# Sheet2.net
KiCad netlist of a schematic drawn in Altium Designer
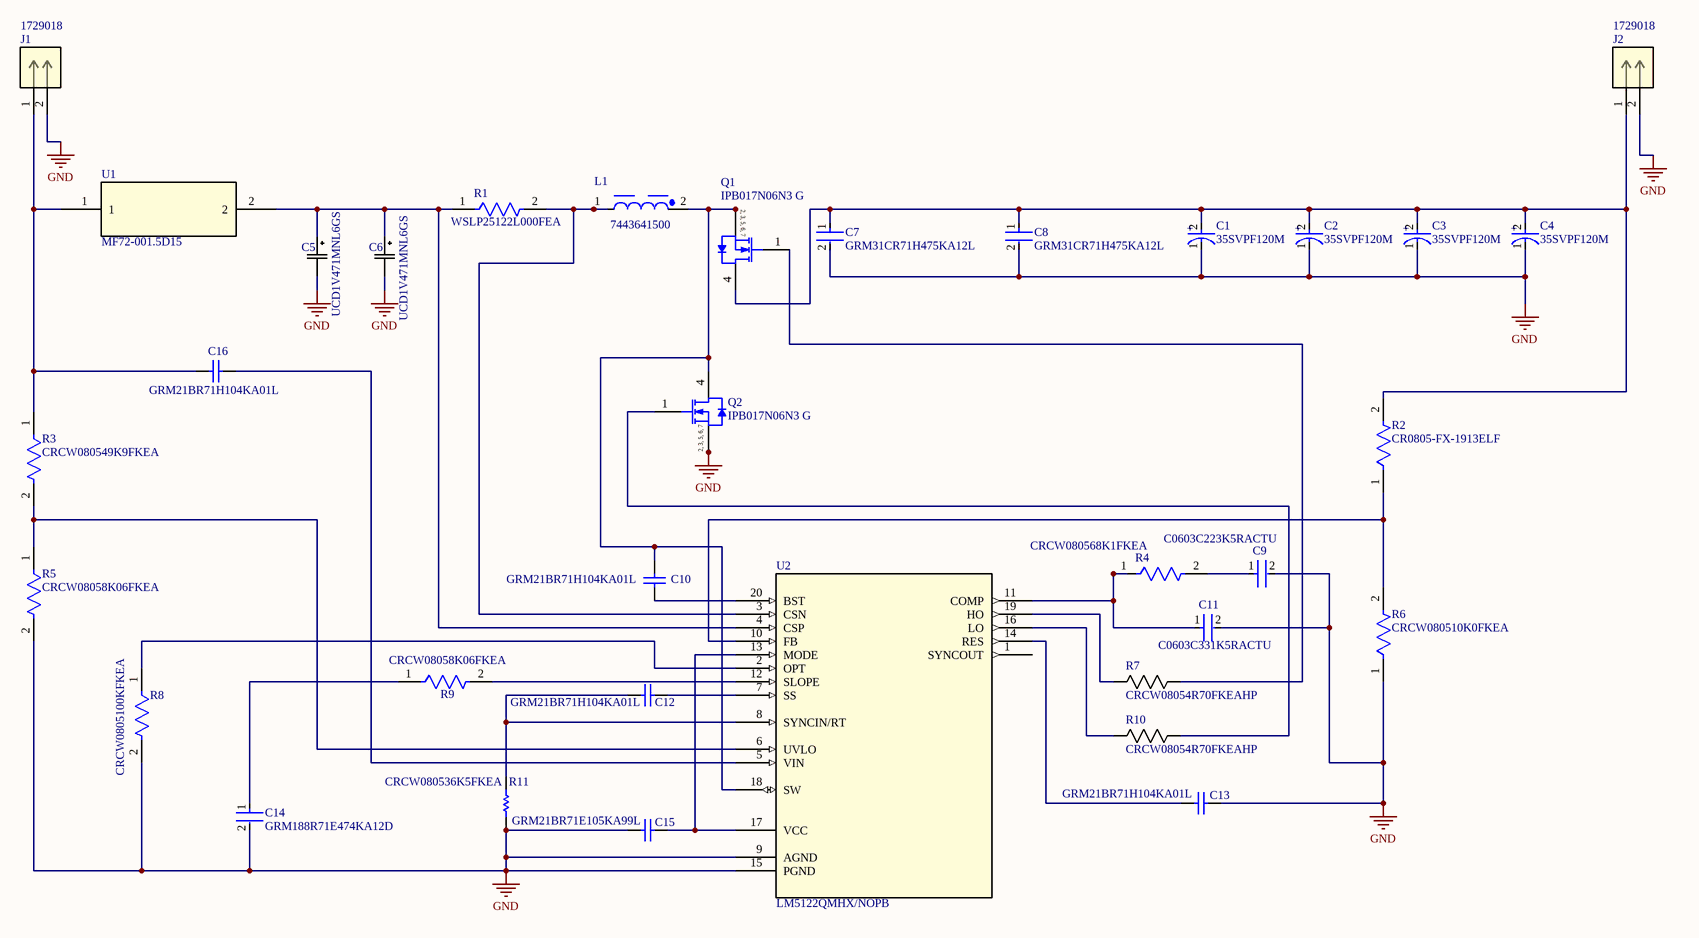
[diagram p0: Sheet2.SchDoc]

(export (version "E")
  (design (tool "Eeschema 10.0.6"))
  (components
    (comp (ref "C1")
      (value "35SVPF120M")
      (footprint "FP-OS-CON-SMT-F12-MFG")
      (description "Conductive Polymer Aluminum Solid Capacitors (OS-CON) 120uF ±20% 35V RADIAL SMT 10x12.6mm")
      (fields (field (name "VOLTAGE") "35V") (field (name "TOLERANCE") "20%"))
      (libsource (lib "Altium Content Vault") (part "a7907c86e72a156c28511143de7831b"))
    )
    (comp (ref "C2")
      (value "35SVPF120M")
      (footprint "FP-OS-CON-SMT-F12-MFG")
      (description "Conductive Polymer Aluminum Solid Capacitors (OS-CON) 120uF ±20% 35V RADIAL SMT 10x12.6mm")
      (fields (field (name "VOLTAGE") "35V") (field (name "TOLERANCE") "20%"))
      (libsource (lib "Altium Content Vault") (part "a7907c86e72a156c28511143de7831b"))
    )
    (comp (ref "C3")
      (value "35SVPF120M")
      (footprint "FP-OS-CON-SMT-F12-MFG")
      (description "Conductive Polymer Aluminum Solid Capacitors (OS-CON) 120uF ±20% 35V RADIAL SMT 10x12.6mm")
      (fields (field (name "VOLTAGE") "35V") (field (name "TOLERANCE") "20%"))
      (libsource (lib "Altium Content Vault") (part "a7907c86e72a156c28511143de7831b"))
    )
    (comp (ref "C4")
      (value "35SVPF120M")
      (footprint "FP-OS-CON-SMT-F12-MFG")
      (description "Conductive Polymer Aluminum Solid Capacitors (OS-CON) 120uF ±20% 35V RADIAL SMT 10x12.6mm")
      (fields (field (name "VOLTAGE") "35V") (field (name "TOLERANCE") "20%"))
      (libsource (lib "Altium Content Vault") (part "a7907c86e72a156c28511143de7831b"))
    )
    (comp (ref "C5")
      (value "UCD1V471MNL6GS")
      (footprint "CAP_UCD_10X13P5_NCH")
      (description "No Description Available")
      (fields (field (name "COPYRIGHT") "Copyright (C) 2026 Ultra Librarian. All rights reserved."))
      (libsource (lib "UCD1V471MNL6GS") (part "UCD1V471MNL6GS"))
    )
    (comp (ref "C6")
      (value "UCD1V471MNL6GS")
      (footprint "CAP_UCD_10X13P5_NCH")
      (description "No Description Available")
      (fields (field (name "COPYRIGHT") "Copyright (C) 2026 Ultra Librarian. All rights reserved."))
      (libsource (lib "UCD1V471MNL6GS") (part "UCD1V471MNL6GS"))
    )
    (comp (ref "C7")
      (value "GRM31CR71H475KA12L")
      (footprint "FP-GRM31C-0_2-e0_3_0_8-IPC_C")
      (description "Chip Multilayer Ceramic Capacitors for General Purpose, 1206, 4.7uF, X7R, 15%, 10%, 50V")
      (fields (field (name "VOLTAGE") "50V") (field (name "TOLERANCE") "10%"))
      (libsource (lib "Altium Content Vault") (part "02cd4be3c70576c341d710602a673aa"))
    )
    (comp (ref "C8")
      (value "GRM31CR71H475KA12L")
      (footprint "FP-GRM31C-0_2-e0_3_0_8-IPC_C")
      (description "Chip Multilayer Ceramic Capacitors for General Purpose, 1206, 4.7uF, X7R, 15%, 10%, 50V")
      (fields (field (name "VOLTAGE") "50V") (field (name "TOLERANCE") "10%"))
      (libsource (lib "Altium Content Vault") (part "02cd4be3c70576c341d710602a673aa"))
    )
    (comp (ref "C9")
      (value "C0603C223K5RACTU")
      (footprint "FP-C0603C-CF-MFG")
      (description "Ceramic Capacitor 0.022Uf 50V, X7R, 10%, 0603, Full Reel")
      (fields
        (field (name "OCTOPART") "https://octopart.com/c0603c223k5ractu-kemet-97352")
        (field (name "TOLERANCE") "0.1")
      )
      (libsource (lib "Altium Content Vault") (part "b4654b650e69147ec39a6b967a45e02"))
    )
    (comp (ref "C10")
      (value "GRM21BR71H104KA01L")
      (footprint "CAPC2013X135X45ML10T25")
      (description "Chip Capacitor, 0.1 uF, +/- 10%, 50 V, -55 to 125 degC, 0805 (2012 Metric), RoHS, Tape and Reel")
      (fields (field (name "VOLTAGE") "50V") (field (name "TOLERANCE") "10%"))
      (libsource (lib "Altium Content Vault") (part "CAP-NP-2"))
    )
    (comp (ref "C11")
      (value "C0603C331K5RACTU")
      (footprint "FP-C0603C-CF-MFG")
      (description "CAP CER 330PF 50V X7R 0603")
      (fields (field (name "MANUFACTURER") "KEMET") (field (name "TOLERANCE") "0.1"))
      (libsource (lib "Altium Content Vault") (part "b4654b650e69147ec39a6b967a45e02"))
    )
    (comp (ref "C12")
      (value "GRM21BR71H104KA01L")
      (footprint "CAPC2013X135X45ML10T25")
      (description "Chip Capacitor, 0.1 uF, +/- 10%, 50 V, -55 to 125 degC, 0805 (2012 Metric), RoHS, Tape and Reel")
      (fields (field (name "VOLTAGE") "50V") (field (name "TOLERANCE") "10%"))
      (libsource (lib "Altium Content Vault") (part "CAP-NP-2"))
    )
    (comp (ref "C13")
      (value "GRM21BR71H104KA01L")
      (footprint "CAPC2013X135X45ML10T25")
      (description "Chip Capacitor, 0.1 uF, +/- 10%, 50 V, -55 to 125 degC, 0805 (2012 Metric), RoHS, Tape and Reel")
      (fields (field (name "VOLTAGE") "50V") (field (name "TOLERANCE") "10%"))
      (libsource (lib "Altium Content Vault") (part "CAP-NP-2"))
    )
    (comp (ref "C14")
      (value "GRM188R71E474KA12D")
      (footprint "FP-GRM188-0_1-e0_2_0_5-MFG")
      (description "Chip Multilayer Ceramic Capacitors for General Purpose, 0603, 0.47uF, X7R, 15%, 10%, 25V")
      (fields (field (name "TOLERANCE") "10%") (field (name "VOLTAGE") "50V"))
      (libsource (lib "Altium Content Vault") (part "11868f565c42a9108669ba33697ecf6"))
    )
    (comp (ref "C15")
      (value "GRM21BR71E105KA99L")
      (footprint "CAPC2013X140X45NL15T25")
      (fields (field (name "MANUFACTURER") "Murata"))
      (libsource (lib "Altium Content Vault") (part "CAP"))
    )
    (comp (ref "C16")
      (value "GRM21BR71H104KA01L")
      (footprint "CAPC2013X135X45ML10T25")
      (description "Chip Capacitor, 0.1 uF, +/- 10%, 50 V, -55 to 125 degC, 0805 (2012 Metric), RoHS, Tape and Reel")
      (fields (field (name "VOLTAGE") "50V") (field (name "TOLERANCE") "10%"))
      (libsource (lib "Altium Content Vault") (part "CAP-NP-2"))
    )
    (comp (ref "J1")
      (value "1729018")
      (footprint "CONN_1729018_PXC")
      (fields (field (name "COPYRIGHT") "Copyright (C) 2025 Ultra Librarian. All rights reserved."))
      (libsource (lib "1729018") (part "1729018"))
    )
    (comp (ref "J2")
      (value "1729018")
      (footprint "CONN_1729018_PXC")
      (fields (field (name "COPYRIGHT") "Copyright (C) 2025 Ultra Librarian. All rights reserved."))
      (libsource (lib "1729018") (part "1729018"))
    )
    (comp (ref "L1")
      (value "7443641500")
      (footprint "WE-HCF_2818")
      (description "PowerChoke Shielded Wirewound 15uH 15% 100KHz Ferrite 30A 0.00264Ohm DCR Automotive Tray")
      (fields (field (name "TOLERANCE") "15%"))
      (libsource (lib "Altium Content Vault") (part "WE-HCF_2818"))
    )
    (comp (ref "Q1")
      (value "IPB017N06N3 G")
      (footprint "INF-PG-TO-263-7-2_N")
      (fields (field (name "MANUFACTURER") "Infineon"))
      (libsource (lib "Altium Content Vault") (part "INF-NEMOS-GSSDSSS-7"))
    )
    (comp (ref "Q2")
      (value "IPB017N06N3 G")
      (footprint "INF-PG-TO-263-7-2_N")
      (fields (field (name "MANUFACTURER") "Infineon"))
      (libsource (lib "Altium Content Vault") (part "INF-NEMOS-GSSDSSS-7"))
    )
    (comp (ref "R1")
      (value "WSLP25122L000FEA")
      (footprint "FP-WSLP2512-0R001-0R0049-MFG")
      (description "RES 0.002 OHM 1% 3W 2512")
      (fields (field (name "TOLERANCE") "1%"))
      (libsource (lib "Altium Content Vault") (part "1029c3af85768c4190bb7ad29bc67b5"))
    )
    (comp (ref "R2")
      (value "CR0805-FX-1913ELF")
      (footprint "FP-CR0805-IPC_B")
      (description "Thick Film Chip Resistors 0805 191kΩ 0.125W 1% 100ppm/°C")
      (fields (field (name "TOLERANCE") "1%"))
      (libsource (lib "Altium Content Vault") (part "1029c3af85768c4190bb7ad29bc67b5"))
    )
    (comp (ref "R3")
      (value "CRCW080549K9FKEA")
      (footprint "FP-CRCW0805-e3-IPC_C")
      (description "RES Thick Film, 49.9kΩ, 1%, 0.125W, 100ppm/°C, 0805")
      (fields (field (name "TOLERANCE") "1%"))
      (libsource (lib "Altium Content Vault") (part "1029c3af85768c4190bb7ad29bc67b5"))
    )
    (comp (ref "R4")
      (value "CRCW080568K1FKEA")
      (footprint "FP-CRCW0805-e3-MFG")
      (description "RES Thick Film, 68.1kΩ, 1%, 0.125W, 100ppm/°C, 0805")
      (fields (field (name "TOLERANCE") "1%"))
      (libsource (lib "Altium Content Vault") (part "1029c3af85768c4190bb7ad29bc67b5"))
    )
    (comp (ref "R5")
      (value "CRCW08058K06FKEA")
      (footprint "FP-CRCW0805-e3-MFG")
      (description "RES Thick Film, 8.06kΩ, 1%, 0.125W, 100ppm/°C, 0805")
      (fields (field (name "TOLERANCE") "1%"))
      (libsource (lib "Altium Content Vault") (part "1029c3af85768c4190bb7ad29bc67b5"))
    )
    (comp (ref "R6")
      (value "CRCW080510K0FKEA")
      (footprint "FP-CRCW0805-e3-IPC_A")
      (description "RES Thick Film, 10kΩ, 1%, 0.125W, 100ppm/°C, 0805")
      (fields (field (name "TOLERANCE") "1%"))
      (libsource (lib "Altium Content Vault") (part "1029c3af85768c4190bb7ad29bc67b5"))
    )
    (comp (ref "R7")
      (value "CRCW08054R70FKEAHP")
      (footprint "RES_CRCW_0805_VIS")
      (description "CRCW0805-HP 100 4R7 1% ET1 E3")
      (fields (field (name "COPYRIGHT") "Copyright (C) 2025 Ultra Librarian. All rights reserved."))
      (libsource (lib "CRCW08054R70FKEAHP") (part "CRCW08054R70FKEAHP"))
    )
    (comp (ref "R8")
      (value "CRCW0805100KFKEA")
      (footprint "FP-CRCW0805-e3-MFG")
      (description "RES Thick Film, 100kΩ, 1%, 0.125W, 100ppm/°C, 0805")
      (fields (field (name "TOLERANCE") "1%"))
      (libsource (lib "Altium Content Vault") (part "1029c3af85768c4190bb7ad29bc67b5"))
    )
    (comp (ref "R9")
      (value "CRCW08058K06FKEA")
      (footprint "FP-CRCW0805-e3-MFG")
      (description "RES Thick Film, 8.06kΩ, 1%, 0.125W, 100ppm/°C, 0805")
      (fields (field (name "TOLERANCE") "1%"))
      (libsource (lib "Altium Content Vault") (part "1029c3af85768c4190bb7ad29bc67b5"))
    )
    (comp (ref "R10")
      (value "CRCW08054R70FKEAHP")
      (footprint "RES_CRCW_0805_VIS")
      (description "CRCW0805-HP 100 4R7 1% ET1 E3")
      (fields (field (name "COPYRIGHT") "Copyright (C) 2025 Ultra Librarian. All rights reserved."))
      (libsource (lib "CRCW08054R70FKEAHP") (part "CRCW08054R70FKEAHP"))
    )
    (comp (ref "R11")
      (value "CRCW080536K5FKEA")
      (footprint "RESC2013X50X30ML20T20")
      (fields (field (name "MANUFACTURER") "Vishay Dale"))
      (libsource (lib "Altium Content Vault") (part "RES"))
    )
    (comp (ref "U1")
      (value "MF72-001.5D15")
      (footprint "MF72-001.5D15_CTM")
      (description "Description")
      (fields (field (name "COPYRIGHT") "Copyright (C) 2026 Ultra Librarian. All rights reserved."))
      (libsource (lib "MF72-001P5D15") (part "MF72-001.5D15"))
    )
    (comp (ref "U2")
      (value "LM5122QMHX/NOPB")
      (footprint "PWP20_3P0X4P2-M")
      (fields (field (name "COPYRIGHT") "Copyright (C) 2026 Ultra Librarian. All rights reserved."))
      (libsource (lib "LM5122QMHXNOPB") (part "LM5122QMHXNOPB"))
    )
  )
  (nets
    (net (code "1") (name "GND") (class "Default")
      (node (ref "C1") (pin "1") (pinfunction "C_1") (pintype "passive"))
      (node (ref "C11") (pin "2") (pinfunction "2_2") (pintype "passive"))
      (node (ref "C13") (pin "2") (pinfunction "2_2") (pintype "passive"))
      (node (ref "C14") (pin "2") (pinfunction "2_2") (pintype "passive"))
      (node (ref "C15") (pin "1") (pinfunction "1_1") (pintype "passive"))
      (node (ref "C2") (pin "1") (pinfunction "C_1") (pintype "passive"))
      (node (ref "C3") (pin "1") (pinfunction "C_1") (pintype "passive"))
      (node (ref "C4") (pin "1") (pinfunction "C_1") (pintype "passive"))
      (node (ref "C5") (pin "2") (pinfunction "2_2") (pintype "passive"))
      (node (ref "C6") (pin "2") (pinfunction "2_2") (pintype "passive"))
      (node (ref "C7") (pin "2") (pinfunction "2_2") (pintype "passive"))
      (node (ref "C8") (pin "2") (pinfunction "2_2") (pintype "passive"))
      (node (ref "C9") (pin "2") (pinfunction "2_2") (pintype "passive"))
      (node (ref "J1") (pin "2") (pinfunction "2_2") (pintype "passive"))
      (node (ref "J2") (pin "2") (pinfunction "2_2") (pintype "passive"))
      (node (ref "Q2") (pin "2") (pinfunction "SOURCE_2") (pintype "passive"))
      (node (ref "Q2") (pin "3") (pinfunction "SOURCE_3") (pintype "passive"))
      (node (ref "Q2") (pin "5") (pinfunction "SOURCE_5") (pintype "passive"))
      (node (ref "Q2") (pin "6") (pinfunction "SOURCE_6") (pintype "passive"))
      (node (ref "Q2") (pin "7") (pinfunction "SOURCE_7") (pintype "passive"))
      (node (ref "R11") (pin "1") (pinfunction "1_1") (pintype "passive"))
      (node (ref "R5") (pin "2") (pinfunction "2_2") (pintype "passive"))
      (node (ref "R6") (pin "1") (pinfunction "1_1") (pintype "passive"))
      (node (ref "R8") (pin "2") (pinfunction "2_2") (pintype "passive"))
      (node (ref "U2") (pin "15") (pinfunction "PGND_15") (pintype "power_in"))
      (node (ref "U2") (pin "9") (pinfunction "AGND_9") (pintype "power_in"))
    )
    (net (code "2") (name "Net-(C1-A)") (class "Default")
      (node (ref "C1") (pin "2") (pinfunction "A_2") (pintype "passive"))
      (node (ref "C2") (pin "2") (pinfunction "A_2") (pintype "passive"))
      (node (ref "C3") (pin "2") (pinfunction "A_2") (pintype "passive"))
      (node (ref "C4") (pin "2") (pinfunction "A_2") (pintype "passive"))
      (node (ref "C7") (pin "1") (pinfunction "1_1") (pintype "passive"))
      (node (ref "C8") (pin "1") (pinfunction "1_1") (pintype "passive"))
      (node (ref "J2") (pin "1") (pinfunction "1_1") (pintype "passive"))
      (node (ref "Q1") (pin "4") (pinfunction "DRAIN_4") (pintype "passive"))
      (node (ref "R2") (pin "2") (pinfunction "2_2") (pintype "passive"))
    )
    (net (code "3") (name "Net-(C9-Pad1)") (class "Default")
      (node (ref "C9") (pin "1") (pinfunction "1_1") (pintype "passive"))
      (node (ref "R4") (pin "2") (pinfunction "2_2") (pintype "passive"))
    )
    (net (code "4") (name "Net-(C14-Pad1)") (class "Default")
      (node (ref "C14") (pin "1") (pinfunction "1_1") (pintype "passive"))
      (node (ref "R9") (pin "1") (pinfunction "1_1") (pintype "passive"))
    )
    (net (code "5") (name "Net-(C16-Pad1)") (class "Default")
      (node (ref "C16") (pin "1") (pinfunction "1_1") (pintype "passive"))
      (node (ref "J1") (pin "1") (pinfunction "1_1") (pintype "passive"))
      (node (ref "R3") (pin "1") (pinfunction "1_1") (pintype "passive"))
      (node (ref "U1") (pin "1") (pinfunction "1_1") (pintype "passive"))
    )
    (net (code "6") (name "Net-(Q1-GATE)") (class "Default")
      (node (ref "Q1") (pin "1") (pinfunction "GATE_1") (pintype "passive"))
      (node (ref "R7") (pin "1") (pinfunction "1_1") (pintype "passive"))
    )
    (net (code "7") (name "Net-(Q2-DRAIN)") (class "Default")
      (node (ref "C10") (pin "1") (pinfunction "1_1") (pintype "passive"))
      (node (ref "L1") (pin "2") (pinfunction "2_2") (pintype "passive"))
      (node (ref "Q1") (pin "2") (pinfunction "SOURCE_2") (pintype "passive"))
      (node (ref "Q1") (pin "3") (pinfunction "SOURCE_3") (pintype "passive"))
      (node (ref "Q1") (pin "5") (pinfunction "SOURCE_5") (pintype "passive"))
      (node (ref "Q1") (pin "6") (pinfunction "SOURCE_6") (pintype "passive"))
      (node (ref "Q1") (pin "7") (pinfunction "SOURCE_7") (pintype "passive"))
      (node (ref "Q2") (pin "4") (pinfunction "DRAIN_4") (pintype "passive"))
      (node (ref "U2") (pin "18") (pinfunction "SW_18") (pintype "bidirectional"))
    )
    (net (code "8") (name "Net-(Q2-GATE)") (class "Default")
      (node (ref "Q2") (pin "1") (pinfunction "GATE_1") (pintype "passive"))
      (node (ref "R10") (pin "1") (pinfunction "1_1") (pintype "passive"))
    )
    (net (code "9") (name "Net-(U2-BST)") (class "Default")
      (node (ref "C10") (pin "2") (pinfunction "2_2") (pintype "passive"))
      (node (ref "U2") (pin "20") (pinfunction "BST_20") (pintype "input"))
    )
    (net (code "10") (name "Net-(U2-COMP)") (class "Default")
      (node (ref "C11") (pin "1") (pinfunction "1_1") (pintype "passive"))
      (node (ref "R4") (pin "1") (pinfunction "1_1") (pintype "passive"))
      (node (ref "U2") (pin "11") (pinfunction "COMP_11") (pintype "output"))
    )
    (net (code "11") (name "Net-(U2-CSN)") (class "Default")
      (node (ref "L1") (pin "1") (pinfunction "1_1") (pintype "passive"))
      (node (ref "R1") (pin "2") (pinfunction "2_2") (pintype "passive"))
      (node (ref "U2") (pin "3") (pinfunction "CSN_3") (pintype "input"))
    )
    (net (code "12") (name "Net-(U2-CSP)") (class "Default")
      (node (ref "C5") (pin "1") (pinfunction "1_1") (pintype "passive"))
      (node (ref "C6") (pin "1") (pinfunction "1_1") (pintype "passive"))
      (node (ref "R1") (pin "1") (pinfunction "1_1") (pintype "passive"))
      (node (ref "U1") (pin "2") (pinfunction "2_2") (pintype "passive"))
      (node (ref "U2") (pin "4") (pinfunction "CSP_4") (pintype "input"))
    )
    (net (code "13") (name "Net-(U2-FB)") (class "Default")
      (node (ref "R2") (pin "1") (pinfunction "1_1") (pintype "passive"))
      (node (ref "R6") (pin "2") (pinfunction "2_2") (pintype "passive"))
      (node (ref "U2") (pin "10") (pinfunction "FB_10") (pintype "input"))
    )
    (net (code "14") (name "Net-(U2-HO)") (class "Default")
      (node (ref "R7") (pin "2") (pinfunction "2_2") (pintype "passive"))
      (node (ref "U2") (pin "19") (pinfunction "HO_19") (pintype "output"))
    )
    (net (code "15") (name "Net-(U2-LO)") (class "Default")
      (node (ref "R10") (pin "2") (pinfunction "2_2") (pintype "passive"))
      (node (ref "U2") (pin "16") (pinfunction "LO_16") (pintype "output"))
    )
    (net (code "16") (name "Net-(U2-MODE)") (class "Default")
      (node (ref "C15") (pin "2") (pinfunction "2_2") (pintype "passive"))
      (node (ref "U2") (pin "13") (pinfunction "MODE_13") (pintype "input"))
      (node (ref "U2") (pin "17") (pinfunction "VCC_17") (pintype "power_in"))
    )
    (net (code "17") (name "Net-(U2-OPT)") (class "Default")
      (node (ref "R8") (pin "1") (pinfunction "1_1") (pintype "passive"))
      (node (ref "U2") (pin "2") (pinfunction "OPT_2") (pintype "input"))
    )
    (net (code "18") (name "Net-(U2-RES)") (class "Default")
      (node (ref "C13") (pin "1") (pinfunction "1_1") (pintype "passive"))
      (node (ref "U2") (pin "14") (pinfunction "RES_14") (pintype "output"))
    )
    (net (code "19") (name "Net-(U2-SLOPE)") (class "Default")
      (node (ref "R9") (pin "2") (pinfunction "2_2") (pintype "passive"))
      (node (ref "U2") (pin "12") (pinfunction "SLOPE_12") (pintype "input"))
    )
    (net (code "20") (name "Net-(U2-SS)") (class "Default")
      (node (ref "C12") (pin "2") (pinfunction "2_2") (pintype "passive"))
      (node (ref "U2") (pin "7") (pinfunction "SS_7") (pintype "input"))
    )
    (net (code "21") (name "Net-(U2-SYNCIN{slash}RT)") (class "Default")
      (node (ref "C12") (pin "1") (pinfunction "1_1") (pintype "passive"))
      (node (ref "R11") (pin "2") (pinfunction "2_2") (pintype "passive"))
      (node (ref "U2") (pin "8") (pinfunction "SYNCIN/RT_8") (pintype "input"))
    )
    (net (code "22") (name "Net-(U2-UVLO)") (class "Default")
      (node (ref "R3") (pin "2") (pinfunction "2_2") (pintype "passive"))
      (node (ref "R5") (pin "1") (pinfunction "1_1") (pintype "passive"))
      (node (ref "U2") (pin "6") (pinfunction "UVLO_6") (pintype "input"))
    )
    (net (code "23") (name "Net-(U2-VIN)") (class "Default")
      (node (ref "C16") (pin "2") (pinfunction "2_2") (pintype "passive"))
      (node (ref "U2") (pin "5") (pinfunction "VIN_5") (pintype "input"))
    )
    (net (code "24") (name "unconnected-(U2-SYNCOUT-Pad1)") (class "Default")
      (node (ref "U2") (pin "1") (pinfunction "SYNCOUT_1") (pintype "output"))
    )
  )
)
